# inputs.net
KiCad netlist of a schematic drawn in Altium Designer
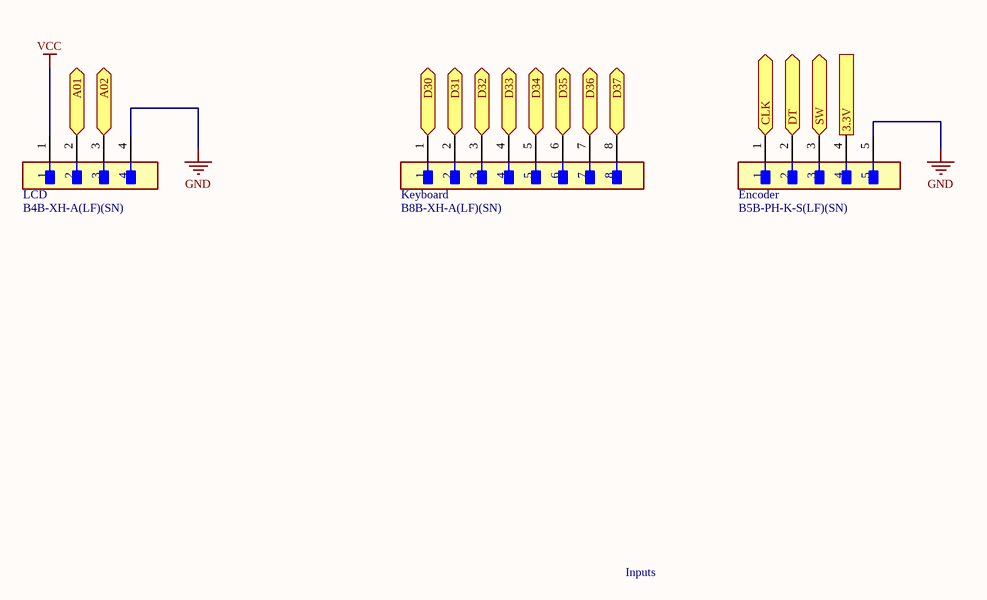
[diagram p0: inputs.SchDoc]

(export (version "E")
  (design (tool "Eeschema 10.0.6"))
  (components
    (comp (ref "Encoder")
      (value "B5B-PH-K-S(LF)(SN)")
      (footprint "FP-B5B-PH-K-S_LF_SN-MFG")
      (description "CONN HEADER VERT 5POS 2MM")
      (libsource (lib "Altium Content Vault") (part "bf93c07fd2649a848d0ec8585582aab"))
    )
    (comp (ref "Keyboard")
      (value "B8B-XH-A(LF)(SN)")
      (footprint "FP-B8B-XH-A_LF_SN-MFG")
      (description "CONN HEADER VERT 8POS 2.5MM")
      (libsource (lib "Altium Content Vault") (part "99ec2b232beb5d2356d4d77f6a047f0"))
    )
    (comp (ref "LCD")
      (value "B4B-XH-A(LF)(SN)")
      (footprint "FP-B4B-XH-A_LF_SN-MFG")
      (description "CONN HEADER VERT 4POS 2.5MM")
      (libsource (lib "Altium Content Vault") (part "299a8cea1bdcbc3624fe62c390fa72c"))
    )
  )
  (nets
    (net (code "1") (name "/3.3V") (class "Default")
      (node (ref "Encoder") (pin "4") (pinfunction "4_4") (pintype "passive"))
    )
    (net (code "2") (name "/A01") (class "Default")
      (node (ref "LCD") (pin "2") (pinfunction "2_2") (pintype "passive"))
    )
    (net (code "3") (name "/A02") (class "Default")
      (node (ref "LCD") (pin "3") (pinfunction "3_3") (pintype "passive"))
    )
    (net (code "4") (name "/CLK") (class "Default")
      (node (ref "Encoder") (pin "1") (pinfunction "1_1") (pintype "passive"))
    )
    (net (code "5") (name "/D30") (class "Default")
      (node (ref "Keyboard") (pin "1") (pinfunction "1_1") (pintype "passive"))
    )
    (net (code "6") (name "/D31") (class "Default")
      (node (ref "Keyboard") (pin "2") (pinfunction "2_2") (pintype "passive"))
    )
    (net (code "7") (name "/D32") (class "Default")
      (node (ref "Keyboard") (pin "3") (pinfunction "3_3") (pintype "passive"))
    )
    (net (code "8") (name "/D33") (class "Default")
      (node (ref "Keyboard") (pin "4") (pinfunction "4_4") (pintype "passive"))
    )
    (net (code "9") (name "/D34") (class "Default")
      (node (ref "Keyboard") (pin "5") (pinfunction "5_5") (pintype "passive"))
    )
    (net (code "10") (name "/D35") (class "Default")
      (node (ref "Keyboard") (pin "6") (pinfunction "6_6") (pintype "passive"))
    )
    (net (code "11") (name "/D36") (class "Default")
      (node (ref "Keyboard") (pin "7") (pinfunction "7_7") (pintype "passive"))
    )
    (net (code "12") (name "/D37") (class "Default")
      (node (ref "Keyboard") (pin "8") (pinfunction "8_8") (pintype "passive"))
    )
    (net (code "13") (name "/DT") (class "Default")
      (node (ref "Encoder") (pin "2") (pinfunction "2_2") (pintype "passive"))
    )
    (net (code "14") (name "/SW") (class "Default")
      (node (ref "Encoder") (pin "3") (pinfunction "3_3") (pintype "passive"))
    )
    (net (code "15") (name "GND") (class "Default")
      (node (ref "Encoder") (pin "5") (pinfunction "5_5") (pintype "passive"))
      (node (ref "LCD") (pin "4") (pinfunction "4_4") (pintype "passive"))
    )
    (net (code "16") (name "VCC") (class "Default")
      (node (ref "LCD") (pin "1") (pinfunction "1_1") (pintype "passive"))
    )
  )
)
